# power_supply.net
KiCad netlist of a schematic drawn in EAGLE
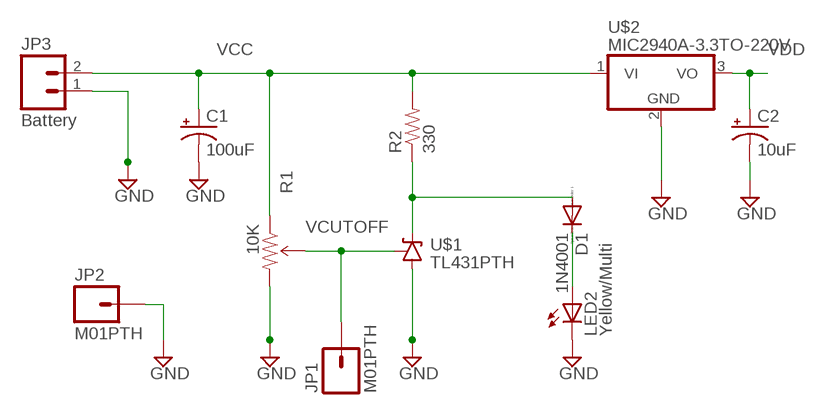
[diagram p0: schematic, sheet 1]

(export (version "E")
  (design (tool "Eeschema 10.0.6"))
  (components
    (comp (ref "C1")
      (value "100uF")
      (footprint "eagle-import:E3,5-8")
      (libsource (lib "eagle-import") (part "CPOL-USE3.5-8"))
    )
    (comp (ref "C2")
      (value "10uF")
      (footprint "eagle-import:E2,5-5")
      (libsource (lib "eagle-import") (part "CPOL-USE2.5-5"))
    )
    (comp (ref "D1")
      (value "1N4001")
      (footprint "eagle-import:DO41-10")
      (libsource (lib "eagle-import") (part "1N4004"))
    )
    (comp (ref "JP1")
      (value "M01PTH")
      (footprint "eagle-import:1X01")
      (libsource (lib "eagle-import") (part "M01PTH"))
    )
    (comp (ref "JP2")
      (value "M01PTH")
      (footprint "eagle-import:1X01")
      (libsource (lib "eagle-import") (part "M01PTH"))
    )
    (comp (ref "JP3")
      (value "Battery")
      (footprint "eagle-import:1X02")
      (libsource (lib "eagle-import") (part "M02PTH"))
    )
    (comp (ref "LED2")
      (value "Yellow/Multi")
      (footprint "eagle-import:LED5MM")
      (libsource (lib "eagle-import") (part "LED5MM"))
    )
    (comp (ref "R1")
      (value "10K")
      (footprint "eagle-import:3386U")
      (fields (field (name "CREATOR") "Brandon") (field (name "REVIEWER1") "Chris"))
      (libsource (lib "eagle-import") (part "TRIMPOT-PTH-KNOB"))
    )
    (comp (ref "R2")
      (value "330")
      (footprint "eagle-import:AXIAL-0.3")
      (libsource (lib "eagle-import") (part "RESISTORAXIAL-0.3"))
    )
    (comp (ref "U$1")
      (value "TL431PTH")
      (footprint "eagle-import:TO-92")
      (libsource (lib "eagle-import") (part "TL431PTH"))
    )
    (comp (ref "U$2")
      (value "MIC2940A-3.3TO-220V")
      (footprint "eagle-import:TO-220V")
      (libsource (lib "eagle-import") (part "MIC2940A-3.3TO-220V"))
    )
  )
  (nets
    (net (code "1") (name "/VCC") (class "Default")
      (node (ref "C1") (pin "+") (pinfunction "+_+") (pintype "passive"))
      (node (ref "JP3") (pin "2") (pinfunction "2_2") (pintype "passive"))
      (node (ref "R1") (pin "1") (pinfunction "CCW_1") (pintype "passive"))
      (node (ref "R2") (pin "P$2") (pinfunction "2_P$2") (pintype "passive"))
      (node (ref "U$2") (pin "1") (pinfunction "VI_1") (pintype "input"))
    )
    (net (code "2") (name "/VCUTOFF") (class "Default")
      (node (ref "JP1") (pin "1") (pinfunction "1_1") (pintype "passive"))
      (node (ref "R1") (pin "2") (pinfunction "WIPER_2") (pintype "passive"))
      (node (ref "U$1") (pin "1") (pinfunction "R_1") (pintype "bidirectional"))
    )
    (net (code "3") (name "/VDD") (class "Default")
      (node (ref "C2") (pin "+") (pinfunction "+_+") (pintype "passive"))
      (node (ref "U$2") (pin "3") (pinfunction "VO_3") (pintype "passive"))
    )
    (net (code "4") (name "GND") (class "Default")
      (node (ref "C1") (pin "-") (pinfunction "-_-") (pintype "passive"))
      (node (ref "C2") (pin "-") (pinfunction "-_-") (pintype "passive"))
      (node (ref "JP2") (pin "1") (pinfunction "1_1") (pintype "passive"))
      (node (ref "JP3") (pin "1") (pinfunction "1_1") (pintype "passive"))
      (node (ref "LED2") (pin "K") (pinfunction "C_K") (pintype "passive"))
      (node (ref "R1") (pin "3") (pinfunction "CW_3") (pintype "passive"))
      (node (ref "U$1") (pin "2") (pinfunction "A_2") (pintype "passive"))
      (node (ref "U$2") (pin "2") (pinfunction "GND_2") (pintype "passive"))
    )
    (net (code "5") (name "Net-(D1-PadC)") (class "Default")
      (node (ref "D1") (pin "C") (pinfunction "C_C") (pintype "passive"))
      (node (ref "LED2") (pin "A") (pinfunction "A_A") (pintype "passive"))
    )
    (net (code "6") (name "Net-(R2-1)") (class "Default")
      (node (ref "D1") (pin "A") (pinfunction "A_A") (pintype "passive"))
      (node (ref "R2") (pin "P$1") (pinfunction "1_P$1") (pintype "passive"))
      (node (ref "U$1") (pin "3") (pinfunction "C_3") (pintype "passive"))
    )
  )
)
